# obc_rtc.net
KiCad netlist of a schematic drawn in Altium Designer
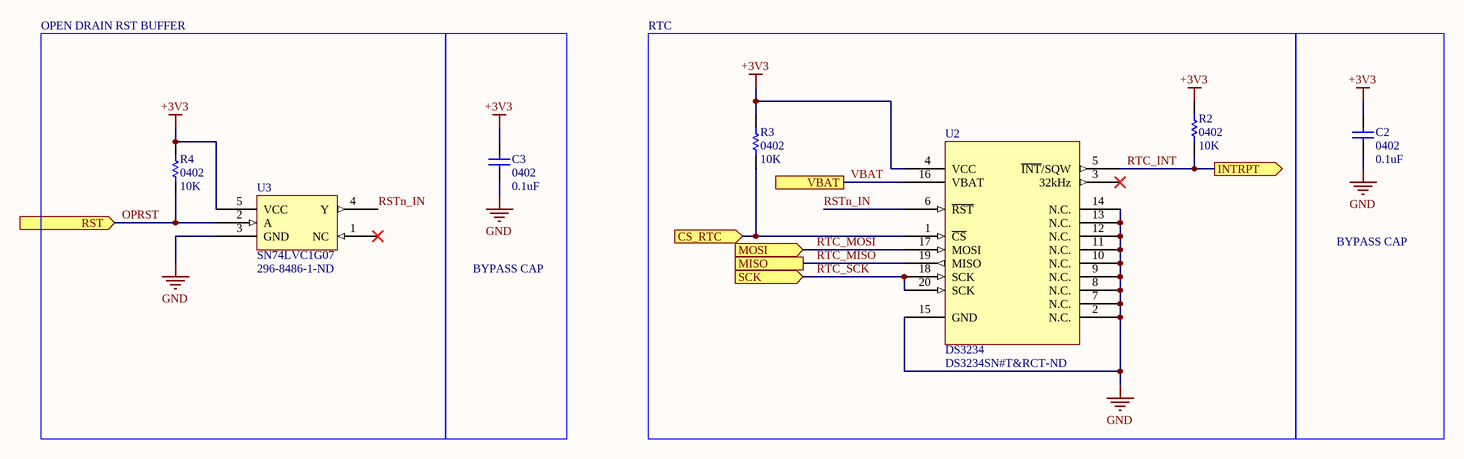
[diagram p0: obc_rtc.SchDoc]

(export (version "E")
  (design (tool "Eeschema 10.0.6"))
  (components
    (comp (ref "C2")
      (value "0402")
      (footprint "CAP0402R")
      (description "0402 capacitor")
      (fields (field (name "ALTIUM_VALUE") "0.1uF"))
      (libsource (lib "heron-general") (part "CAP0402"))
    )
    (comp (ref "C3")
      (value "0402")
      (footprint "CAP0402R")
      (description "0402 capacitor")
      (fields (field (name "ALTIUM_VALUE") "0.1uF"))
      (libsource (lib "heron-general") (part "CAP0402"))
    )
    (comp (ref "R2")
      (value "0402")
      (footprint "RES0402R")
      (description "0402 resistor")
      (fields (field (name "ALTIUM_VALUE") "10K"))
      (libsource (lib "heron-general") (part "RES0402"))
    )
    (comp (ref "R3")
      (value "0402")
      (footprint "RES0402R")
      (description "0402 resistor")
      (fields (field (name "ALTIUM_VALUE") "10K"))
      (libsource (lib "heron-general") (part "RES0402"))
    )
    (comp (ref "R4")
      (value "0402")
      (footprint "RES0402R")
      (description "0402 resistor")
      (fields (field (name "ALTIUM_VALUE") "10K"))
      (libsource (lib "heron-general") (part "RES0402"))
    )
    (comp (ref "U2")
      (value "DS3234")
      (footprint "SOIC127P1032X265-20")
      (description "SPI bus RTC with integrated crystal and SRAM")
      (fields (field (name "SUPPLIER PART NUMBER 2") "DS3234SN#T&RCT-ND"))
      (libsource (lib "heron-general") (part "DS3234"))
    )
    (comp (ref "U3")
      (value "SN74LVC1G07")
      (footprint "SOT65P210X110-5N")
      (description "Single element non-inverting open drain buffer")
      (fields (field (name "SUPPLIER PART NUMBER 1") "296-8486-1-ND"))
      (libsource (lib "ICs") (part "SN74LVC1G07"))
    )
  )
  (nets
    (net (code "1") (name "+3V3") (class "Default")
      (node (ref "C2") (pin "2") (pinfunction "2_2") (pintype "passive"))
      (node (ref "C3") (pin "2") (pinfunction "2_2") (pintype "passive"))
      (node (ref "R2") (pin "2") (pinfunction "2_2") (pintype "passive"))
      (node (ref "R3") (pin "2") (pinfunction "2_2") (pintype "passive"))
      (node (ref "R4") (pin "2") (pinfunction "2_2") (pintype "passive"))
      (node (ref "U2") (pin "4") (pinfunction "VCC_4") (pintype "power_in"))
      (node (ref "U3") (pin "5") (pinfunction "VCC_5") (pintype "power_in"))
    )
    (net (code "2") (name "/CS_RTC") (class "Default")
      (node (ref "R3") (pin "1") (pinfunction "1_1") (pintype "passive"))
      (node (ref "U2") (pin "1") (pinfunction "~{CS}_1") (pintype "input"))
    )
    (net (code "3") (name "/OPRST") (class "Default")
      (node (ref "R4") (pin "1") (pinfunction "1_1") (pintype "passive"))
      (node (ref "U3") (pin "2") (pinfunction "A_2") (pintype "input"))
    )
    (net (code "4") (name "/RSTn_IN") (class "Default")
      (node (ref "U2") (pin "6") (pinfunction "~{RST}_6") (pintype "input"))
      (node (ref "U3") (pin "4") (pinfunction "Y_4") (pintype "output"))
    )
    (net (code "5") (name "/RTC_INT") (class "Default")
      (node (ref "R2") (pin "1") (pinfunction "1_1") (pintype "passive"))
      (node (ref "U2") (pin "5") (pinfunction "~{INT}/SQW_5") (pintype "output"))
    )
    (net (code "6") (name "/RTC_MISO") (class "Default")
      (node (ref "U2") (pin "19") (pinfunction "MISO_19") (pintype "output"))
    )
    (net (code "7") (name "/RTC_MOSI") (class "Default")
      (node (ref "U2") (pin "17") (pinfunction "MOSI_17") (pintype "input"))
    )
    (net (code "8") (name "/RTC_SCK") (class "Default")
      (node (ref "U2") (pin "18") (pinfunction "SCK_18") (pintype "input"))
      (node (ref "U2") (pin "20") (pinfunction "SCK_20") (pintype "input"))
    )
    (net (code "9") (name "/VBAT") (class "Default")
      (node (ref "U2") (pin "16") (pinfunction "VBAT_16") (pintype "power_in"))
    )
    (net (code "10") (name "GND") (class "Default")
      (node (ref "C2") (pin "1") (pinfunction "1_1") (pintype "passive"))
      (node (ref "C3") (pin "1") (pinfunction "1_1") (pintype "passive"))
      (node (ref "U2") (pin "10") (pinfunction "N.C._10") (pintype "passive"))
      (node (ref "U2") (pin "11") (pinfunction "N.C._11") (pintype "passive"))
      (node (ref "U2") (pin "12") (pinfunction "N.C._12") (pintype "passive"))
      (node (ref "U2") (pin "13") (pinfunction "N.C._13") (pintype "passive"))
      (node (ref "U2") (pin "14") (pinfunction "N.C._14") (pintype "passive"))
      (node (ref "U2") (pin "15") (pinfunction "GND_15") (pintype "power_in"))
      (node (ref "U2") (pin "2") (pinfunction "N.C._2") (pintype "passive"))
      (node (ref "U2") (pin "7") (pinfunction "N.C._7") (pintype "passive"))
      (node (ref "U2") (pin "8") (pinfunction "N.C._8") (pintype "passive"))
      (node (ref "U2") (pin "9") (pinfunction "N.C._9") (pintype "passive"))
      (node (ref "U3") (pin "3") (pinfunction "GND_3") (pintype "power_in"))
    )
    (net (code "11") (name "unconnected-(U2-32kHz-Pad3)") (class "Default")
      (node (ref "U2") (pin "3") (pinfunction "32kHz_3") (pintype "output+no_connect"))
    )
    (net (code "12") (name "unconnected-(U3-NC-Pad1)") (class "Default")
      (node (ref "U3") (pin "1") (pinfunction "NC_1") (pintype "input+no_connect"))
    )
  )
)
